# M452X3.net
KiCad netlist of a schematic drawn in EAGLE
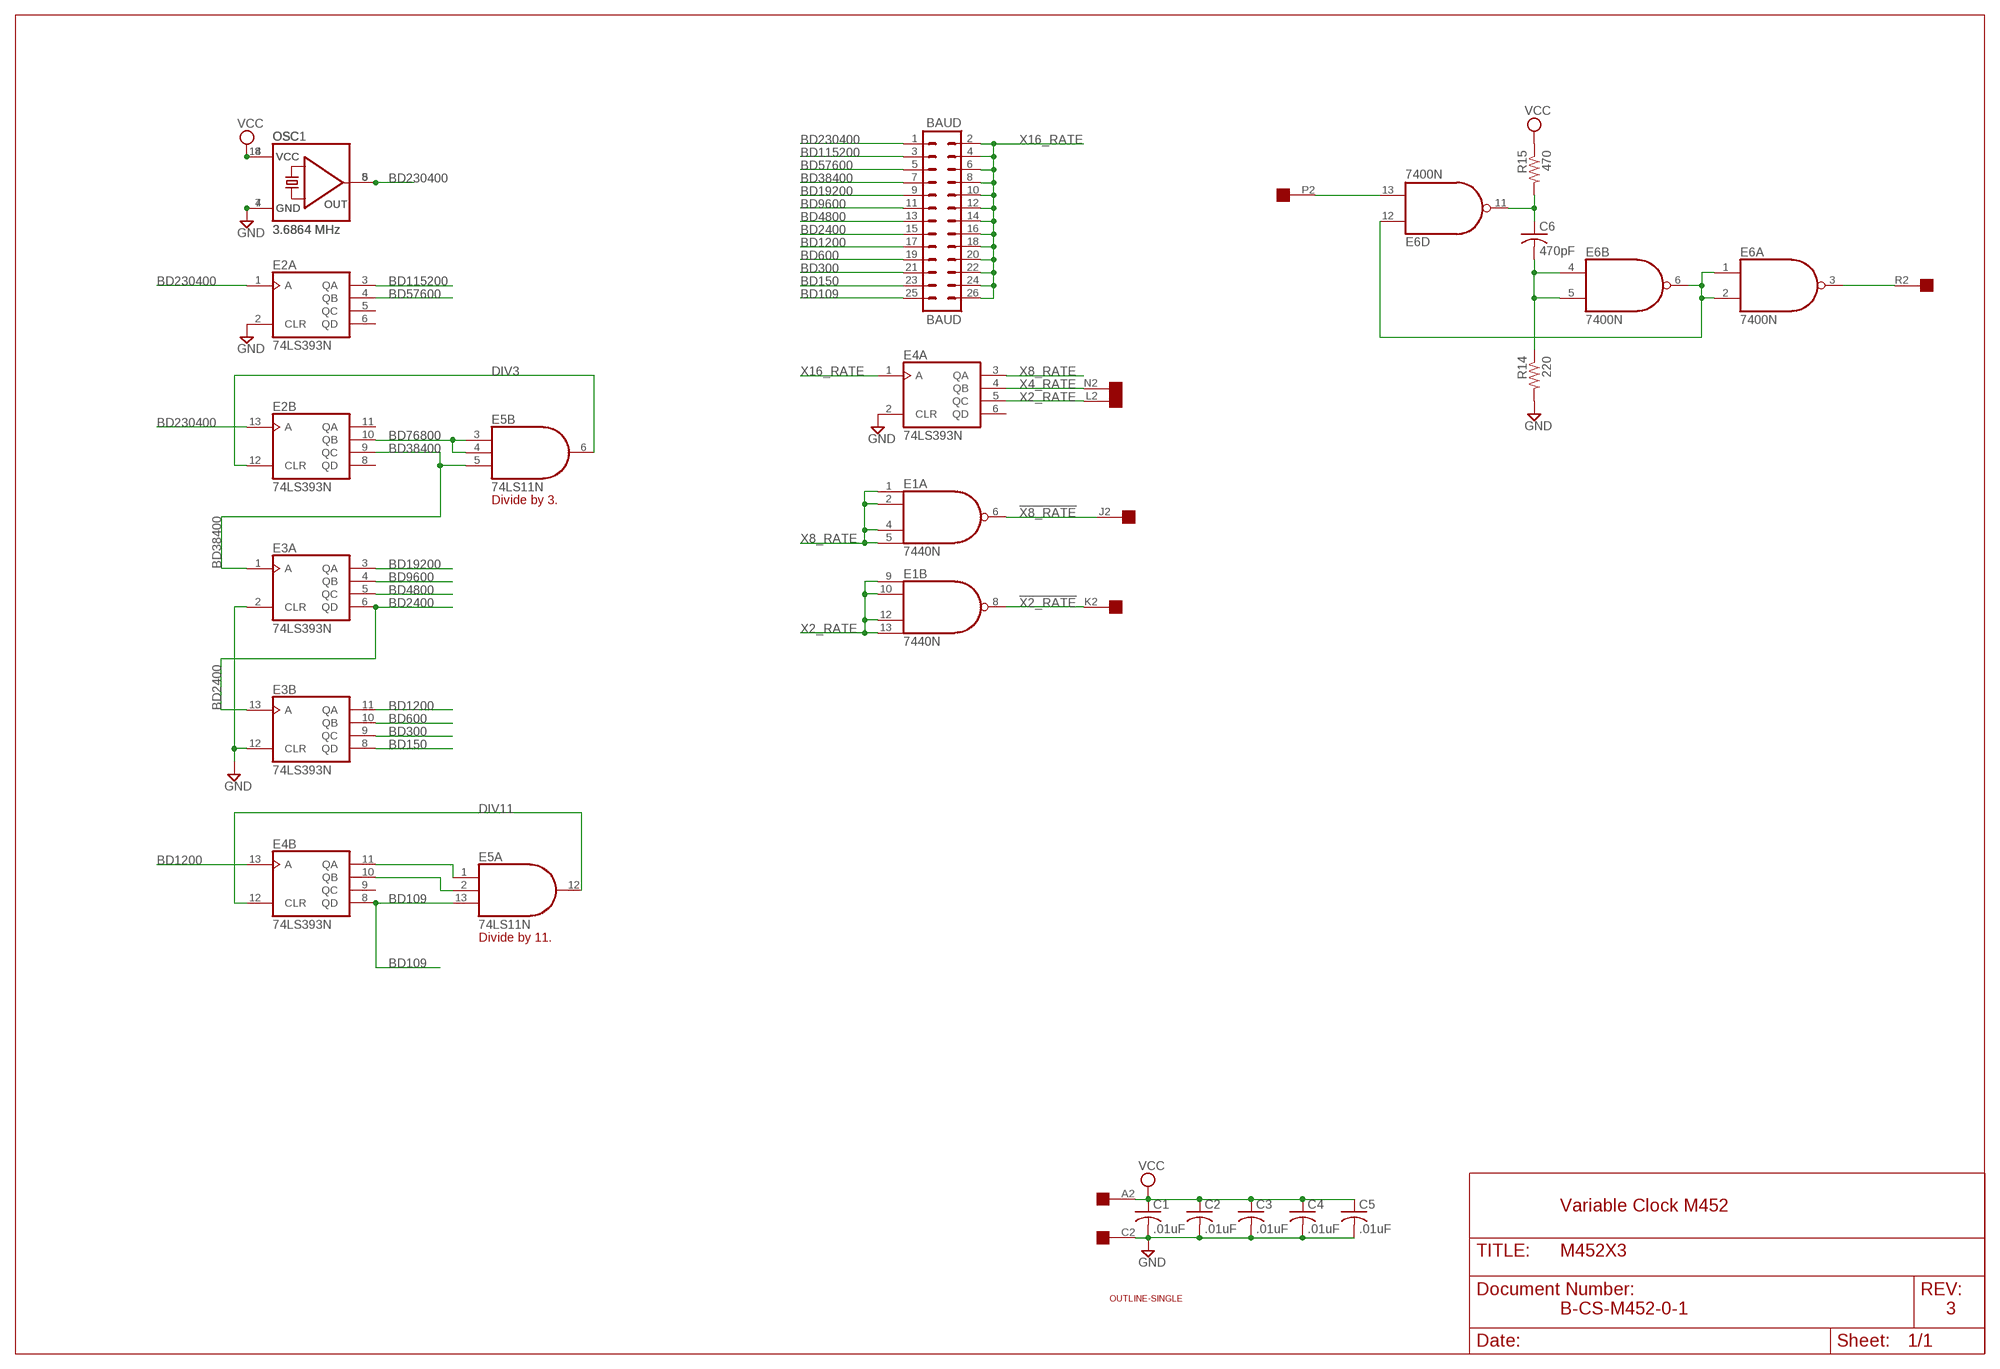
[diagram p0: schematic, sheet 1]

(export (version "E")
  (design (tool "Eeschema 10.0.6"))
  (components
    (comp (ref "BAUD")
      (value "BAUD")
      (footprint "eagle-import:MA13-2")
      (libsource (lib "eagle-import") (part "MA13-2"))
    )
    (comp (ref "C1")
      (value ".01uF")
      (footprint "eagle-import:C050-025X075")
      (libsource (lib "eagle-import") (part "C-US050-025X075"))
    )
    (comp (ref "C2")
      (value ".01uF")
      (footprint "eagle-import:C050-025X075")
      (libsource (lib "eagle-import") (part "C-US050-025X075"))
    )
    (comp (ref "C3")
      (value ".01uF")
      (footprint "eagle-import:C050-025X075")
      (libsource (lib "eagle-import") (part "C-US050-025X075"))
    )
    (comp (ref "C4")
      (value ".01uF")
      (footprint "eagle-import:C050-025X075")
      (libsource (lib "eagle-import") (part "C-US050-025X075"))
    )
    (comp (ref "C5")
      (value ".01uF")
      (footprint "eagle-import:C050-025X075")
      (libsource (lib "eagle-import") (part "C-US050-025X075"))
    )
    (comp (ref "C6")
      (value "470pF")
      (footprint "eagle-import:C075-032X103")
      (libsource (lib "eagle-import") (part "C-US075-032X103"))
    )
    (comp (ref "E1")
      (value "7440N")
      (footprint "eagle-import:DIL14")
      (libsource (lib "eagle-import") (part "7420NS"))
    )
    (comp (ref "E2")
      (value "74LS393N")
      (footprint "eagle-import:DIL14")
      (libsource (lib "eagle-import") (part "74393NLS"))
    )
    (comp (ref "E3")
      (value "74LS393N")
      (footprint "eagle-import:DIL14")
      (libsource (lib "eagle-import") (part "74393NLS"))
    )
    (comp (ref "E4")
      (value "74LS393N")
      (footprint "eagle-import:DIL14")
      (libsource (lib "eagle-import") (part "74393NLS"))
    )
    (comp (ref "E5")
      (value "74LS11N")
      (footprint "eagle-import:DIL14")
      (libsource (lib "eagle-import") (part "7411NLS"))
    )
    (comp (ref "E6")
      (value "7400N")
      (footprint "eagle-import:DIL14")
      (libsource (lib "eagle-import") (part "7400NLS"))
    )
    (comp (ref "OSC")
      (value "3.6864 MHz")
      (footprint "eagle-import:DIL08S")
      (libsource (lib "eagle-import") (part "QG5460"))
    )
    (comp (ref "OSC1")
      (value "3.6864 MHz")
      (footprint "eagle-import:DIL14S")
      (libsource (lib "eagle-import") (part "QG5860"))
    )
    (comp (ref "R14")
      (value "220")
      (footprint "eagle-import:0207_10")
      (libsource (lib "eagle-import") (part "R-US_0207/10"))
    )
    (comp (ref "R15")
      (value "470")
      (footprint "eagle-import:0207_10")
      (libsource (lib "eagle-import") (part "R-US_0207/10"))
    )
    (comp (ref "U$1")
      (value "OUTLINE-SINGLE")
      (footprint "eagle-import:SINGLE")
      (libsource (lib "eagle-import") (part "OUTLINE-SINGLE"))
    )
    (comp (ref "U$2")
      (value "EDGE-1")
      (footprint "eagle-import:EDGE-CON1")
      (libsource (lib "eagle-import") (part "EDGE-1"))
    )
  )
  (nets
    (net (code "1") (name "/BD109") (class "Default")
      (node (ref "BAUD") (pin "25") (pinfunction "25_25") (pintype "passive"))
      (node (ref "E4") (pin "8") (pinfunction "QD_8") (pintype "output"))
      (node (ref "E5") (pin "13") (pinfunction "I2_13") (pintype "input"))
    )
    (net (code "2") (name "/BD150") (class "Default")
      (node (ref "BAUD") (pin "23") (pinfunction "23_23") (pintype "passive"))
      (node (ref "E3") (pin "8") (pinfunction "QD_8") (pintype "output"))
    )
    (net (code "3") (name "/BD300") (class "Default")
      (node (ref "BAUD") (pin "21") (pinfunction "21_21") (pintype "passive"))
      (node (ref "E3") (pin "9") (pinfunction "QC_9") (pintype "output"))
    )
    (net (code "4") (name "/BD600") (class "Default")
      (node (ref "BAUD") (pin "19") (pinfunction "19_19") (pintype "passive"))
      (node (ref "E3") (pin "10") (pinfunction "QB_10") (pintype "output"))
    )
    (net (code "5") (name "/BD1200") (class "Default")
      (node (ref "BAUD") (pin "17") (pinfunction "17_17") (pintype "passive"))
      (node (ref "E3") (pin "11") (pinfunction "QA_11") (pintype "output"))
      (node (ref "E4") (pin "13") (pinfunction "A_13") (pintype "input"))
    )
    (net (code "6") (name "/BD2400") (class "Default")
      (node (ref "BAUD") (pin "15") (pinfunction "15_15") (pintype "passive"))
      (node (ref "E3") (pin "13") (pinfunction "A_13") (pintype "input"))
      (node (ref "E3") (pin "6") (pinfunction "QD_6") (pintype "output"))
    )
    (net (code "7") (name "/BD4800") (class "Default")
      (node (ref "BAUD") (pin "13") (pinfunction "13_13") (pintype "passive"))
      (node (ref "E3") (pin "5") (pinfunction "QC_5") (pintype "output"))
    )
    (net (code "8") (name "/BD9600") (class "Default")
      (node (ref "BAUD") (pin "11") (pinfunction "11_11") (pintype "passive"))
      (node (ref "E3") (pin "4") (pinfunction "QB_4") (pintype "output"))
    )
    (net (code "9") (name "/BD19200") (class "Default")
      (node (ref "BAUD") (pin "9") (pinfunction "9_9") (pintype "passive"))
      (node (ref "E3") (pin "3") (pinfunction "QA_3") (pintype "output"))
    )
    (net (code "10") (name "/BD38400") (class "Default")
      (node (ref "BAUD") (pin "7") (pinfunction "7_7") (pintype "passive"))
      (node (ref "E2") (pin "9") (pinfunction "QC_9") (pintype "output"))
      (node (ref "E3") (pin "1") (pinfunction "A_1") (pintype "input"))
      (node (ref "E5") (pin "5") (pinfunction "I2_5") (pintype "input"))
    )
    (net (code "11") (name "/BD57600") (class "Default")
      (node (ref "BAUD") (pin "5") (pinfunction "5_5") (pintype "passive"))
      (node (ref "E2") (pin "4") (pinfunction "QB_4") (pintype "output"))
    )
    (net (code "12") (name "/BD76800") (class "Default")
      (node (ref "E2") (pin "10") (pinfunction "QB_10") (pintype "output"))
      (node (ref "E5") (pin "3") (pinfunction "I0_3") (pintype "input"))
      (node (ref "E5") (pin "4") (pinfunction "I1_4") (pintype "input"))
    )
    (net (code "13") (name "/BD115200") (class "Default")
      (node (ref "BAUD") (pin "3") (pinfunction "3_3") (pintype "passive"))
      (node (ref "E2") (pin "3") (pinfunction "QA_3") (pintype "output"))
    )
    (net (code "14") (name "/BD230400") (class "Default")
      (node (ref "BAUD") (pin "1") (pinfunction "1_1") (pintype "passive"))
      (node (ref "E2") (pin "1") (pinfunction "A_1") (pintype "input"))
      (node (ref "E2") (pin "13") (pinfunction "A_13") (pintype "input"))
      (node (ref "OSC") (pin "5") (pinfunction "OUT_5") (pintype "output"))
      (node (ref "OSC1") (pin "8") (pinfunction "OUT_8") (pintype "output"))
    )
    (net (code "15") (name "/DIV3") (class "Default")
      (node (ref "E2") (pin "12") (pinfunction "CLR_12") (pintype "input"))
      (node (ref "E5") (pin "6") (pinfunction "O_6") (pintype "output"))
    )
    (net (code "16") (name "/DIV11") (class "Default")
      (node (ref "E4") (pin "12") (pinfunction "CLR_12") (pintype "input"))
      (node (ref "E5") (pin "12") (pinfunction "O_12") (pintype "output"))
    )
    (net (code "17") (name "/X2_RATE") (class "Default")
      (node (ref "E1") (pin "10") (pinfunction "I1_10") (pintype "input"))
      (node (ref "E1") (pin "12") (pinfunction "I2_12") (pintype "input"))
      (node (ref "E1") (pin "13") (pinfunction "I3_13") (pintype "input"))
      (node (ref "E1") (pin "9") (pinfunction "I0_9") (pintype "input"))
      (node (ref "E4") (pin "5") (pinfunction "QC_5") (pintype "output"))
      (node (ref "U$2") (pin "L2") (pinfunction "1_L2") (pintype "bidirectional"))
    )
    (net (code "18") (name "/X4_RATE") (class "Default")
      (node (ref "E4") (pin "4") (pinfunction "QB_4") (pintype "output"))
      (node (ref "U$2") (pin "N2") (pinfunction "1_N2") (pintype "bidirectional"))
    )
    (net (code "19") (name "/X8_RATE") (class "Default")
      (node (ref "E1") (pin "1") (pinfunction "I0_1") (pintype "input"))
      (node (ref "E1") (pin "2") (pinfunction "I1_2") (pintype "input"))
      (node (ref "E1") (pin "4") (pinfunction "I2_4") (pintype "input"))
      (node (ref "E1") (pin "5") (pinfunction "I3_5") (pintype "input"))
      (node (ref "E4") (pin "3") (pinfunction "QA_3") (pintype "output"))
    )
    (net (code "20") (name "/X16_RATE") (class "Default")
      (node (ref "BAUD") (pin "10") (pinfunction "10_10") (pintype "passive"))
      (node (ref "BAUD") (pin "12") (pinfunction "12_12") (pintype "passive"))
      (node (ref "BAUD") (pin "14") (pinfunction "14_14") (pintype "passive"))
      (node (ref "BAUD") (pin "16") (pinfunction "16_16") (pintype "passive"))
      (node (ref "BAUD") (pin "18") (pinfunction "18_18") (pintype "passive"))
      (node (ref "BAUD") (pin "2") (pinfunction "2_2") (pintype "passive"))
      (node (ref "BAUD") (pin "20") (pinfunction "20_20") (pintype "passive"))
      (node (ref "BAUD") (pin "22") (pinfunction "22_22") (pintype "passive"))
      (node (ref "BAUD") (pin "24") (pinfunction "24_24") (pintype "passive"))
      (node (ref "BAUD") (pin "26") (pinfunction "26_26") (pintype "passive"))
      (node (ref "BAUD") (pin "4") (pinfunction "4_4") (pintype "passive"))
      (node (ref "BAUD") (pin "6") (pinfunction "6_6") (pintype "passive"))
      (node (ref "BAUD") (pin "8") (pinfunction "8_8") (pintype "passive"))
      (node (ref "E4") (pin "1") (pinfunction "A_1") (pintype "input"))
    )
    (net (code "21") (name "/~{X2_RATE}") (class "Default")
      (node (ref "E1") (pin "8") (pinfunction "O_8") (pintype "output"))
      (node (ref "U$2") (pin "K2") (pinfunction "1_K2") (pintype "bidirectional"))
    )
    (net (code "22") (name "/~{X8_RATE}") (class "Default")
      (node (ref "E1") (pin "6") (pinfunction "O_6") (pintype "output"))
      (node (ref "U$2") (pin "J2") (pinfunction "1_J2") (pintype "bidirectional"))
    )
    (net (code "23") (name "GND") (class "Default")
      (node (ref "C1") (pin "2") (pinfunction "2_2") (pintype "passive"))
      (node (ref "C2") (pin "2") (pinfunction "2_2") (pintype "passive"))
      (node (ref "C3") (pin "2") (pinfunction "2_2") (pintype "passive"))
      (node (ref "C4") (pin "2") (pinfunction "2_2") (pintype "passive"))
      (node (ref "C5") (pin "2") (pinfunction "2_2") (pintype "passive"))
      (node (ref "E2") (pin "2") (pinfunction "CLR_2") (pintype "input"))
      (node (ref "E3") (pin "12") (pinfunction "CLR_12") (pintype "input"))
      (node (ref "E3") (pin "2") (pinfunction "CLR_2") (pintype "input"))
      (node (ref "E4") (pin "2") (pinfunction "CLR_2") (pintype "input"))
      (node (ref "OSC") (pin "4") (pinfunction "GND_4") (pintype "power_in"))
      (node (ref "OSC1") (pin "7") (pinfunction "GND_7") (pintype "power_in"))
      (node (ref "R14") (pin "2") (pinfunction "2_2") (pintype "passive"))
      (node (ref "U$2") (pin "C2") (pinfunction "1_C2") (pintype "bidirectional"))
    )
    (net (code "24") (name "Net-(E4B-QA)") (class "Default")
      (node (ref "E4") (pin "11") (pinfunction "QA_11") (pintype "output"))
      (node (ref "E5") (pin "1") (pinfunction "I0_1") (pintype "input"))
    )
    (net (code "25") (name "Net-(E4B-QB)") (class "Default")
      (node (ref "E4") (pin "10") (pinfunction "QB_10") (pintype "output"))
      (node (ref "E5") (pin "2") (pinfunction "I1_2") (pintype "input"))
    )
    (net (code "26") (name "Net-(E6A-I0)") (class "Default")
      (node (ref "E6") (pin "1") (pinfunction "I0_1") (pintype "input"))
      (node (ref "E6") (pin "12") (pinfunction "I0_12") (pintype "input"))
      (node (ref "E6") (pin "2") (pinfunction "I1_2") (pintype "input"))
      (node (ref "E6") (pin "6") (pinfunction "O_6") (pintype "output"))
    )
    (net (code "27") (name "Net-(E6A-O)") (class "Default")
      (node (ref "E6") (pin "3") (pinfunction "O_3") (pintype "output"))
      (node (ref "U$2") (pin "R2") (pinfunction "1_R2") (pintype "bidirectional"))
    )
    (net (code "28") (name "Net-(E6B-I0)") (class "Default")
      (node (ref "C6") (pin "2") (pinfunction "2_2") (pintype "passive"))
      (node (ref "E6") (pin "4") (pinfunction "I0_4") (pintype "input"))
      (node (ref "E6") (pin "5") (pinfunction "I1_5") (pintype "input"))
      (node (ref "R14") (pin "1") (pinfunction "1_1") (pintype "passive"))
    )
    (net (code "29") (name "Net-(E6D-I1)") (class "Default")
      (node (ref "E6") (pin "13") (pinfunction "I1_13") (pintype "input"))
      (node (ref "U$2") (pin "P2") (pinfunction "1_P2") (pintype "bidirectional"))
    )
    (net (code "30") (name "Net-(E6D-O)") (class "Default")
      (node (ref "C6") (pin "1") (pinfunction "1_1") (pintype "passive"))
      (node (ref "E6") (pin "11") (pinfunction "O_11") (pintype "output"))
      (node (ref "R15") (pin "2") (pinfunction "2_2") (pintype "passive"))
    )
    (net (code "31") (name "VCC") (class "Default")
      (node (ref "C1") (pin "1") (pinfunction "1_1") (pintype "passive"))
      (node (ref "C2") (pin "1") (pinfunction "1_1") (pintype "passive"))
      (node (ref "C3") (pin "1") (pinfunction "1_1") (pintype "passive"))
      (node (ref "C4") (pin "1") (pinfunction "1_1") (pintype "passive"))
      (node (ref "C5") (pin "1") (pinfunction "1_1") (pintype "passive"))
      (node (ref "OSC") (pin "8") (pinfunction "VCC_8") (pintype "power_in"))
      (node (ref "OSC1") (pin "14") (pinfunction "VCC_14") (pintype "power_in"))
      (node (ref "R15") (pin "1") (pinfunction "1_1") (pintype "passive"))
      (node (ref "U$2") (pin "A2") (pinfunction "1_A2") (pintype "bidirectional"))
    )
    (net (code "32") (name "unconnected-(E2A-QC-Pad5)") (class "Default")
      (node (ref "E2") (pin "5") (pinfunction "QC_5") (pintype "output"))
    )
    (net (code "33") (name "unconnected-(E2A-QD-Pad6)") (class "Default")
      (node (ref "E2") (pin "6") (pinfunction "QD_6") (pintype "output"))
    )
    (net (code "34") (name "unconnected-(E2B-QA-Pad11)") (class "Default")
      (node (ref "E2") (pin "11") (pinfunction "QA_11") (pintype "output"))
    )
    (net (code "35") (name "unconnected-(E2B-QD-Pad8)") (class "Default")
      (node (ref "E2") (pin "8") (pinfunction "QD_8") (pintype "output"))
    )
    (net (code "36") (name "unconnected-(E4A-QD-Pad6)") (class "Default")
      (node (ref "E4") (pin "6") (pinfunction "QD_6") (pintype "output"))
    )
    (net (code "37") (name "unconnected-(E4B-QC-Pad9)") (class "Default")
      (node (ref "E4") (pin "9") (pinfunction "QC_9") (pintype "output"))
    )
  )
)
